# taj1050.net
KiCad netlist of a schematic drawn in Altium Designer
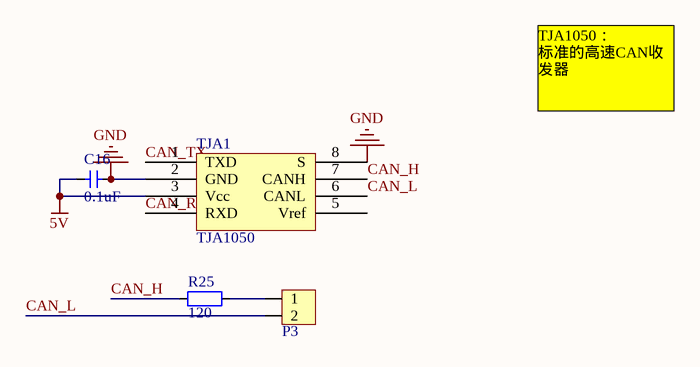
[diagram p0: taj1050.SchDoc]

(export (version "E")
  (design (tool "Eeschema 10.0.6"))
  (components
    (comp (ref "C16")
      (value "0.1uF")
      (footprint "CAP_0603")
      (description "Capacitor")
      (fields (field (name "Comment") "Cap_0603"))
      (libsource (lib "Integrated_Library") (part "Cap_0603"))
    )
    (comp (ref "P3")
      (value "HDR1x2_2.54")
      (footprint "HDR1X2_2.54_180")
      (description "Header")
      (libsource (lib "Integrated_Library") (part "HDR1x2_2.54"))
    )
    (comp (ref "R25")
      (value "120")
      (footprint "RES_0603")
      (description "Resistor")
      (fields (field (name "Comment") "Res_0603"))
      (libsource (lib "Integrated_Library") (part "Res_0603"))
    )
    (comp (ref "TJA1")
      (value "TJA1050")
      (footprint "SOP_E150_8")
      (description "CAN总线收发器")
      (libsource (lib "Libraries_2014_0618") (part "TJA1050"))
    )
  )
  (nets
    (net (code "1") (name "/CAN_H") (class "Default")
      (node (ref "R25") (pin "1") (pinfunction "1_1") (pintype "passive"))
      (node (ref "TJA1") (pin "7") (pinfunction "CANH_7") (pintype "passive"))
    )
    (net (code "2") (name "/CAN_L") (class "Default")
      (node (ref "P3") (pin "2") (pinfunction "2_2") (pintype "passive"))
      (node (ref "TJA1") (pin "6") (pinfunction "CANL_6") (pintype "passive"))
    )
    (net (code "3") (name "/CAN_RX") (class "Default")
      (node (ref "TJA1") (pin "4") (pinfunction "RXD_4") (pintype "passive"))
    )
    (net (code "4") (name "/CAN_TX") (class "Default")
      (node (ref "TJA1") (pin "1") (pinfunction "TXD_1") (pintype "passive"))
    )
    (net (code "5") (name "5V") (class "Default")
      (node (ref "C16") (pin "1") (pinfunction "1_1") (pintype "passive"))
      (node (ref "TJA1") (pin "3") (pinfunction "Vcc_3") (pintype "passive"))
    )
    (net (code "6") (name "GND") (class "Default")
      (node (ref "C16") (pin "2") (pinfunction "2_2") (pintype "passive"))
      (node (ref "TJA1") (pin "2") (pinfunction "GND_2") (pintype "passive"))
      (node (ref "TJA1") (pin "8") (pinfunction "S_8") (pintype "passive"))
    )
    (net (code "7") (name "Net-(P3-Pad1)") (class "Default")
      (node (ref "P3") (pin "1") (pinfunction "1_1") (pintype "passive"))
      (node (ref "R25") (pin "2") (pinfunction "2_2") (pintype "passive"))
    )
    (net (code "8") (name "unconnected-(TJA1-Vref-Pad5)") (class "Default")
      (node (ref "TJA1") (pin "5") (pinfunction "Vref_5") (pintype "passive"))
    )
  )
)
